# Breakouts.net
KiCad netlist of a schematic drawn in Altium Designer
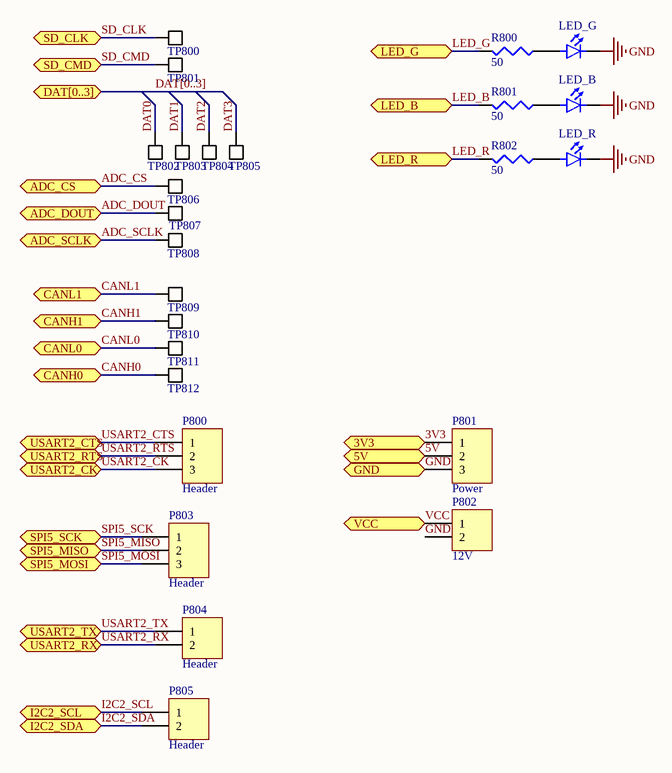
[diagram p0: Breakouts.SchDoc]

(export (version "E")
  (design (tool "Eeschema 10.0.6"))
  (components
    (comp (ref "LED_B")
      (value "LED")
      (footprint "SMD0603 POLARIZED")
      (libsource (lib "Components") (part "LED"))
    )
    (comp (ref "LED_G")
      (value "LED")
      (footprint "SMD0603 POLARIZED")
      (libsource (lib "Components") (part "LED"))
    )
    (comp (ref "LED_R")
      (value "LED")
      (footprint "SMD0603 POLARIZED")
      (libsource (lib "Components") (part "LED"))
    )
    (comp (ref "P800")
      (value "Header")
      (footprint "HEADER 3X1")
      (description "Header, 2-Pin")
      (libsource (lib "Components") (part "Header 3x1"))
    )
    (comp (ref "P801")
      (value "Power")
      (footprint "HEADER 3X1")
      (description "Header, 2-Pin")
      (libsource (lib "Components") (part "Header 3x1"))
    )
    (comp (ref "P802")
      (value "12V")
      (footprint "Header 2x1")
      (description "Header, 2-Pin")
      (libsource (lib "Components") (part "Header 2x1"))
    )
    (comp (ref "P803")
      (value "Header")
      (footprint "HEADER 3X1")
      (description "Header, 2-Pin")
      (libsource (lib "Components") (part "Header 3x1"))
    )
    (comp (ref "P804")
      (value "Header")
      (footprint "Header 2x1")
      (description "Header, 2-Pin")
      (libsource (lib "Components") (part "Header 2x1"))
    )
    (comp (ref "P805")
      (value "Header")
      (footprint "Header 2x1")
      (description "Header, 2-Pin")
      (libsource (lib "Components") (part "Header 2x1"))
    )
    (comp (ref "R800")
      (value "50")
      (footprint "SMD0603")
      (description "Resistor")
      (fields (field (name "Comment") "Res"))
      (libsource (lib "Components") (part "Resistor"))
    )
    (comp (ref "R801")
      (value "50")
      (footprint "SMD0603")
      (description "Resistor")
      (fields (field (name "Comment") "Res"))
      (libsource (lib "Components") (part "Resistor"))
    )
    (comp (ref "R802")
      (value "50")
      (footprint "SMD0603")
      (description "Resistor")
      (fields (field (name "Comment") "Res"))
      (libsource (lib "Components") (part "Resistor"))
    )
    (comp (ref "TP800")
      (value "Test Point")
      (footprint "Test Point")
      (libsource (lib "Components") (part "Test Point"))
    )
    (comp (ref "TP801")
      (value "Test Point")
      (footprint "Test Point")
      (libsource (lib "Components") (part "Test Point"))
    )
    (comp (ref "TP802")
      (value "Test Point")
      (footprint "Test Point")
      (libsource (lib "Components") (part "Test Point"))
    )
    (comp (ref "TP803")
      (value "Test Point")
      (footprint "Test Point")
      (libsource (lib "Components") (part "Test Point"))
    )
    (comp (ref "TP804")
      (value "Test Point")
      (footprint "Test Point")
      (libsource (lib "Components") (part "Test Point"))
    )
    (comp (ref "TP805")
      (value "Test Point")
      (footprint "Test Point")
      (libsource (lib "Components") (part "Test Point"))
    )
    (comp (ref "TP806")
      (value "Test Point")
      (footprint "Test Point")
      (libsource (lib "Components") (part "Test Point"))
    )
    (comp (ref "TP807")
      (value "Test Point")
      (footprint "Test Point")
      (libsource (lib "Components") (part "Test Point"))
    )
    (comp (ref "TP808")
      (value "Test Point")
      (footprint "Test Point")
      (libsource (lib "Components") (part "Test Point"))
    )
    (comp (ref "TP809")
      (value "Test Point")
      (footprint "Test Point")
      (libsource (lib "Components") (part "Test Point"))
    )
    (comp (ref "TP810")
      (value "Test Point")
      (footprint "Test Point")
      (libsource (lib "Components") (part "Test Point"))
    )
    (comp (ref "TP811")
      (value "Test Point")
      (footprint "Test Point")
      (libsource (lib "Components") (part "Test Point"))
    )
    (comp (ref "TP812")
      (value "Test Point")
      (footprint "Test Point")
      (libsource (lib "Components") (part "Test Point"))
    )
  )
  (nets
    (net (code "1") (name "/3V3") (class "Default")
      (node (ref "P801") (pin "1") (pinfunction "1_1") (pintype "passive"))
    )
    (net (code "2") (name "/5V") (class "Default")
      (node (ref "P801") (pin "2") (pinfunction "2_2") (pintype "passive"))
    )
    (net (code "3") (name "/ADC_CS") (class "Default")
      (node (ref "TP806") (pin "1") (pinfunction "1_1") (pintype "passive"))
    )
    (net (code "4") (name "/ADC_DOUT") (class "Default")
      (node (ref "TP807") (pin "1") (pinfunction "1_1") (pintype "passive"))
    )
    (net (code "5") (name "/ADC_SCLK") (class "Default")
      (node (ref "TP808") (pin "1") (pinfunction "1_1") (pintype "passive"))
    )
    (net (code "6") (name "/CANH0") (class "Default")
      (node (ref "TP812") (pin "1") (pinfunction "1_1") (pintype "passive"))
    )
    (net (code "7") (name "/CANH1") (class "Default")
      (node (ref "TP810") (pin "1") (pinfunction "1_1") (pintype "passive"))
    )
    (net (code "8") (name "/CANL0") (class "Default")
      (node (ref "TP811") (pin "1") (pinfunction "1_1") (pintype "passive"))
    )
    (net (code "9") (name "/CANL1") (class "Default")
      (node (ref "TP809") (pin "1") (pinfunction "1_1") (pintype "passive"))
    )
    (net (code "10") (name "/DAT0") (class "Default")
      (node (ref "TP802") (pin "1") (pinfunction "1_1") (pintype "passive"))
    )
    (net (code "11") (name "/DAT1") (class "Default")
      (node (ref "TP803") (pin "1") (pinfunction "1_1") (pintype "passive"))
    )
    (net (code "12") (name "/DAT2") (class "Default")
      (node (ref "TP804") (pin "1") (pinfunction "1_1") (pintype "passive"))
    )
    (net (code "13") (name "/DAT3") (class "Default")
      (node (ref "TP805") (pin "1") (pinfunction "1_1") (pintype "passive"))
    )
    (net (code "15") (name "/I2C2_SCL") (class "Default")
      (node (ref "P805") (pin "1") (pinfunction "1_1") (pintype "passive"))
    )
    (net (code "16") (name "/I2C2_SDA") (class "Default")
      (node (ref "P805") (pin "2") (pinfunction "2_2") (pintype "passive"))
    )
    (net (code "17") (name "/LED_B") (class "Default")
      (node (ref "R801") (pin "2") (pinfunction "2_2") (pintype "passive"))
    )
    (net (code "18") (name "/LED_G") (class "Default")
      (node (ref "R800") (pin "2") (pinfunction "2_2") (pintype "passive"))
    )
    (net (code "19") (name "/LED_R") (class "Default")
      (node (ref "R802") (pin "2") (pinfunction "2_2") (pintype "passive"))
    )
    (net (code "20") (name "/SD_CLK") (class "Default")
      (node (ref "TP800") (pin "1") (pinfunction "1_1") (pintype "passive"))
    )
    (net (code "21") (name "/SD_CMD") (class "Default")
      (node (ref "TP801") (pin "1") (pinfunction "1_1") (pintype "passive"))
    )
    (net (code "22") (name "/SPI5_MISO") (class "Default")
      (node (ref "P803") (pin "2") (pinfunction "2_2") (pintype "passive"))
    )
    (net (code "23") (name "/SPI5_MOSI") (class "Default")
      (node (ref "P803") (pin "3") (pinfunction "3_3") (pintype "passive"))
    )
    (net (code "24") (name "/SPI5_SCK") (class "Default")
      (node (ref "P803") (pin "1") (pinfunction "1_1") (pintype "passive"))
    )
    (net (code "25") (name "/USART2_CK") (class "Default")
      (node (ref "P800") (pin "3") (pinfunction "3_3") (pintype "passive"))
    )
    (net (code "26") (name "/USART2_CTS") (class "Default")
      (node (ref "P800") (pin "1") (pinfunction "1_1") (pintype "passive"))
    )
    (net (code "27") (name "/USART2_RTS") (class "Default")
      (node (ref "P800") (pin "2") (pinfunction "2_2") (pintype "passive"))
    )
    (net (code "28") (name "/USART2_RX") (class "Default")
      (node (ref "P804") (pin "2") (pinfunction "2_2") (pintype "passive"))
    )
    (net (code "29") (name "/USART2_TX") (class "Default")
      (node (ref "P804") (pin "1") (pinfunction "1_1") (pintype "passive"))
    )
    (net (code "30") (name "/VCC") (class "Default")
      (node (ref "P802") (pin "1") (pinfunction "1_1") (pintype "passive"))
    )
    (net (code "31") (name "GND") (class "Default")
      (node (ref "LED_B") (pin "2") (pinfunction "Cathode_(-)_2") (pintype "passive"))
      (node (ref "LED_G") (pin "2") (pinfunction "Cathode_(-)_2") (pintype "passive"))
      (node (ref "LED_R") (pin "2") (pinfunction "Cathode_(-)_2") (pintype "passive"))
      (node (ref "P801") (pin "3") (pinfunction "3_3") (pintype "passive"))
      (node (ref "P802") (pin "2") (pinfunction "2_2") (pintype "passive"))
    )
    (net (code "32") (name "Net-(LED_B-Anode_(+))") (class "Default")
      (node (ref "LED_B") (pin "1") (pinfunction "Anode_(+)_1") (pintype "passive"))
      (node (ref "R801") (pin "1") (pinfunction "1_1") (pintype "passive"))
    )
    (net (code "33") (name "Net-(LED_G-Anode_(+))") (class "Default")
      (node (ref "LED_G") (pin "1") (pinfunction "Anode_(+)_1") (pintype "passive"))
      (node (ref "R800") (pin "1") (pinfunction "1_1") (pintype "passive"))
    )
    (net (code "34") (name "Net-(LED_R-Anode_(+))") (class "Default")
      (node (ref "LED_R") (pin "1") (pinfunction "Anode_(+)_1") (pintype "passive"))
      (node (ref "R802") (pin "1") (pinfunction "1_1") (pintype "passive"))
    )
  )
)
